# design.net
KiCad netlist of a schematic drawn in Altium Designer
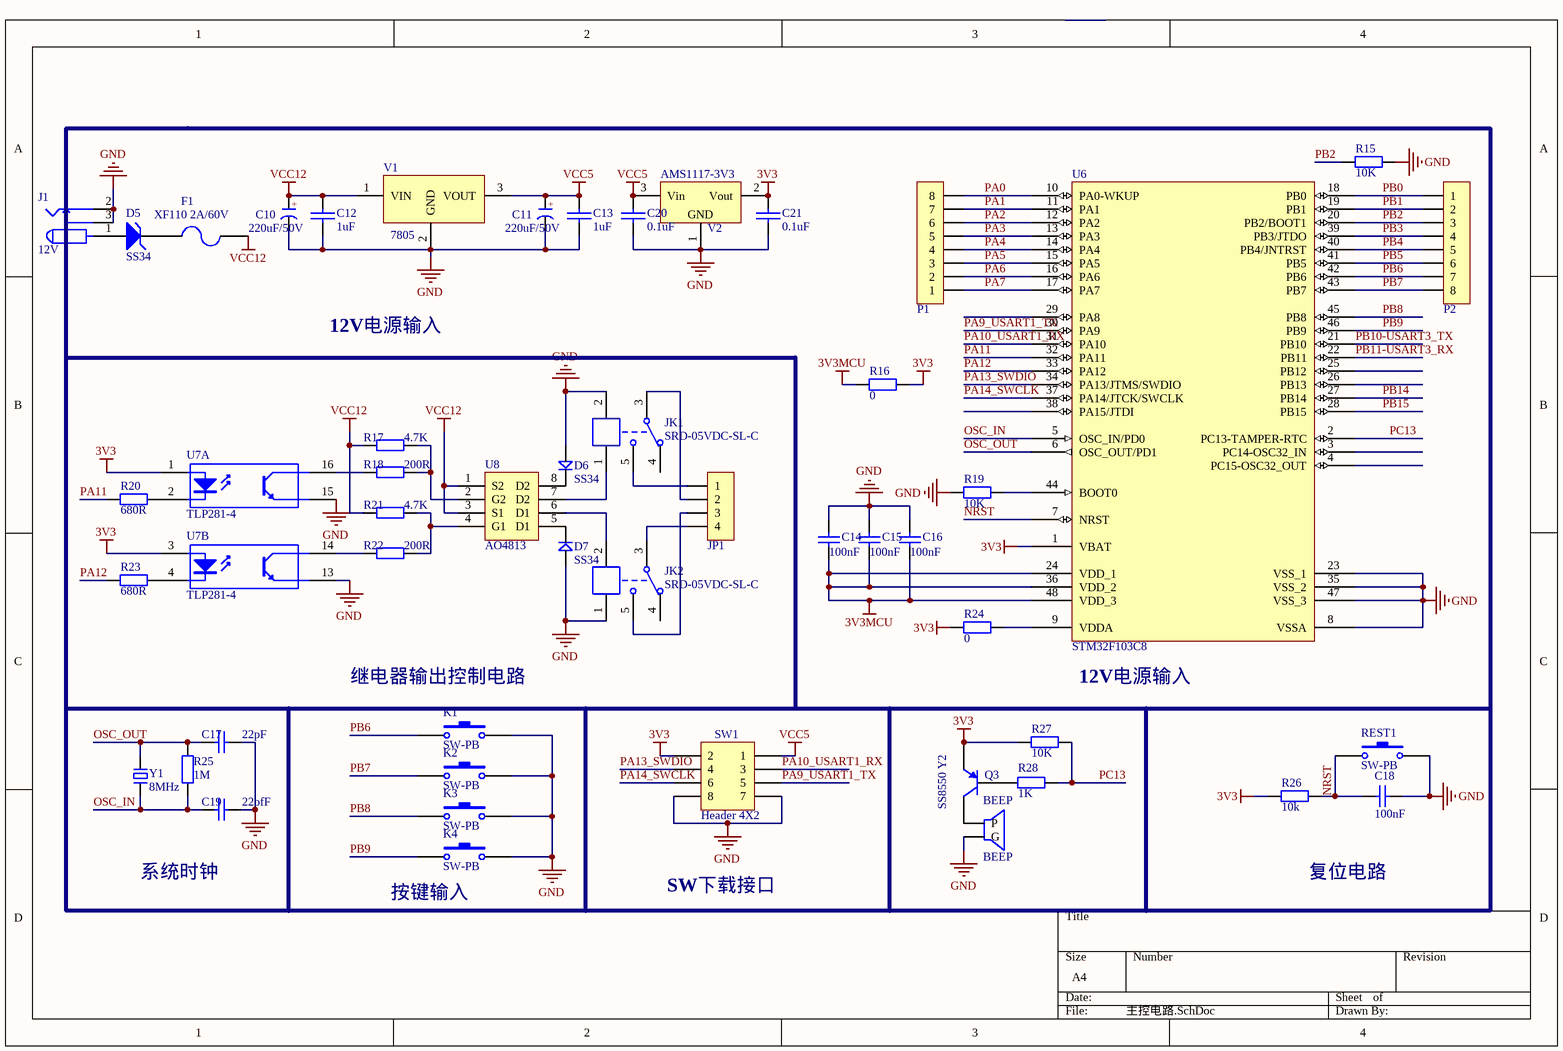
[diagram p0: 主控电路.SchDoc]

(export (version "E")
  (design (tool "Eeschema 10.0.6"))
  (components
    (comp (ref "BEEP")
      (value "BEEP")
      (footprint "BUZZER")
      (libsource (lib "Explorer STM32F407封装库") (part "BEEP"))
    )
    (comp (ref "C10")
      (value "220uF/50V")
      (footprint "CAP 3.5*8*11.5 - BK")
      (description "直插电解电容")
      (fields (field (name "版权归属") "源创客"))
      (libsource (lib "3.1   - 电阻-电容-电感") (part "C-CAP"))
    )
    (comp (ref "C11")
      (value "220uF/50V")
      (footprint "CAP 3.5*8*11.5 - BK")
      (description "直插电解电容")
      (fields (field (name "版权归属") "源创客"))
      (libsource (lib "3.1   - 电阻-电容-电感") (part "C-CAP"))
    )
    (comp (ref "C12")
      (value "1uF")
      (footprint "LC-0603_C")
      (description "Capacitor 0805")
      (libsource (lib "CD's_LIB_2018") (part "0805C"))
    )
    (comp (ref "C13")
      (value "1uF")
      (footprint "LC-0603_C")
      (description "Capacitor 0805")
      (libsource (lib "CD's_LIB_2018") (part "0805C"))
    )
    (comp (ref "C14")
      (value "100nF")
      (footprint "LC-0603_C")
      (description "无极性电容")
      (fields (field (name "PUBLISHER") "Altium Limited"))
      (libsource (lib "liu_2016") (part "Cap"))
    )
    (comp (ref "C15")
      (value "100nF")
      (footprint "LC-0603_C")
      (description "无极性电容")
      (fields (field (name "PUBLISHER") "Altium Limited"))
      (libsource (lib "liu_2016") (part "Cap"))
    )
    (comp (ref "C16")
      (value "100nF")
      (footprint "LC-0603_C")
      (description "无极性电容")
      (fields (field (name "PUBLISHER") "Altium Limited"))
      (libsource (lib "liu_2016") (part "Cap"))
    )
    (comp (ref "C17")
      (value "22pF")
      (footprint "LC-0603_C")
      (description "无极性电容")
      (fields (field (name "PUBLISHER") "Altium Limited"))
      (libsource (lib "liu_2016") (part "Cap"))
    )
    (comp (ref "C18")
      (value "100nF")
      (footprint "LC-0603_C")
      (description "无极性电容")
      (fields (field (name "PUBLISHER") "Altium Limited"))
      (libsource (lib "liu_2016") (part "Cap"))
    )
    (comp (ref "C19")
      (value "22pfF")
      (footprint "LC-0603_C")
      (description "无极性电容")
      (fields (field (name "PUBLISHER") "Altium Limited"))
      (libsource (lib "liu_2016") (part "Cap"))
    )
    (comp (ref "C20")
      (value "0.1uF")
      (footprint "LC-0603_C")
      (description "Capacitor 0805")
      (libsource (lib "CD's_LIB_2018") (part "0805C"))
    )
    (comp (ref "C21")
      (value "0.1uF")
      (footprint "LC-0603_C")
      (description "Capacitor 0805")
      (libsource (lib "CD's_LIB_2018") (part "0805C"))
    )
    (comp (ref "D5")
      (value "SS34")
      (footprint "D1812")
      (description "Zener Diode")
      (libsource (lib "CD's_LIB_2018") (part "1N5822"))
    )
    (comp (ref "D6") (value "SS34") (footprint "D1812") (libsource (lib "Explorer STM32F407封装库") (part "D")))
    (comp (ref "D7") (value "SS34") (footprint "D1812") (libsource (lib "Explorer STM32F407封装库") (part "D")))
    (comp (ref "F1")
      (value "XF110 2A/60V")
      (footprint "FUSE1")
      (description "Fuse")
      (libsource (lib "*") (part "FUSE2"))
    )
    (comp (ref "J1") (value "12V") (footprint "DC10B") (libsource (lib "Explorer STM32F407封装库") (part "POW")))
    (comp (ref "JK1")
      (value "SRD-05VDC-SL-C")
      (footprint "SRD-C_B")
      (description "5V一组转换")
      (fields (field (name "版权归属") "源创客"))
      (libsource (lib "7.1   - 继电器") (part "SRD-05VDC-SL-C"))
    )
    (comp (ref "JK2")
      (value "SRD-05VDC-SL-C")
      (footprint "SRD-C_B")
      (description "5V一组转换")
      (fields (field (name "版权归属") "源创客"))
      (libsource (lib "7.1   - 继电器") (part "SRD-05VDC-SL-C"))
    )
    (comp (ref "JP1")
      (value "HDR-1X4")
      (footprint "KF128-5.08-4P")
      (description "4P接插件")
      (fields (field (name "版权归属") "源创客"))
      (libsource (lib "4.10 - 接插件-脚距5.08") (part "Header 4"))
    )
    (comp (ref "K1")
      (value "SW-PB")
      (footprint "TSW DIP-6*6*5")
      (description "Switch")
      (fields (field (name "PUBLISHER") "Altium Limited"))
      (libsource (lib "PCB_Project") (part "SW-PB"))
    )
    (comp (ref "K2")
      (value "SW-PB")
      (footprint "TSW DIP-6*6*5")
      (description "Switch")
      (fields (field (name "PUBLISHER") "Altium Limited"))
      (libsource (lib "PCB_Project") (part "SW-PB"))
    )
    (comp (ref "K3")
      (value "SW-PB")
      (footprint "TSW DIP-6*6*5")
      (description "Switch")
      (fields (field (name "PUBLISHER") "Altium Limited"))
      (libsource (lib "PCB_Project") (part "SW-PB"))
    )
    (comp (ref "K4")
      (value "SW-PB")
      (footprint "TSW DIP-6*6*5")
      (description "Switch")
      (fields (field (name "PUBLISHER") "Altium Limited"))
      (libsource (lib "PCB_Project") (part "SW-PB"))
    )
    (comp (ref "P1")
      (value "HDR-1X8")
      (footprint "HDR2.54-LI-8P")
      (description "8P接插件")
      (fields (field (name "版权归属") "源创客"))
      (libsource (lib "4.5   - 接插件-脚距2.54") (part "Header 8"))
    )
    (comp (ref "P2")
      (value "HDR-1X8")
      (footprint "HDR2.54-LI-8P")
      (description "8P接插件")
      (fields (field (name "版权归属") "源创客"))
      (libsource (lib "") (part "Header 8_1"))
    )
    (comp (ref "Q3")
      (value "SS8550 Y2")
      (footprint "LC-SOT-23(SOT-23-3)")
      (description "三极管")
      (libsource (lib "Miscellaneous Devices LC") (part "SOT-23 SS8550 Y2"))
    )
    (comp (ref "R15")
      (value "10K")
      (footprint "LC-0603_R")
      (description "贴片电阻")
      (fields (field (name "PUBLISHER") "Altium Limited"))
      (libsource (lib "") (part "Res1_2"))
    )
    (comp (ref "R16")
      (value "0")
      (footprint "LC-0603_R")
      (description "贴片电阻")
      (fields (field (name "PUBLISHER") "Altium Limited"))
      (libsource (lib "liu_2016") (part "Res1"))
    )
    (comp (ref "R17")
      (value "4.7K")
      (footprint "LC-0603_R")
      (description "贴片电阻")
      (libsource (lib "Miscellaneous Devices LC") (part "0603 2.7KΩ (2701) 1%"))
    )
    (comp (ref "R18")
      (value "200R")
      (footprint "LC-0603_R")
      (description "贴片电阻")
      (libsource (lib "CD's_LIB_2018") (part "0603 2.7KΩ (2701) 1%"))
    )
    (comp (ref "R19")
      (value "10K")
      (footprint "LC-0603_R")
      (description "贴片电阻")
      (fields (field (name "PUBLISHER") "Altium Limited"))
      (libsource (lib "liu_2016") (part "Res1"))
    )
    (comp (ref "R20")
      (value "680R")
      (footprint "LC-0603_R")
      (description "贴片电阻")
      (libsource (lib "CD's_LIB_2018") (part "0603 2.7KΩ (2701) 1%"))
    )
    (comp (ref "R21")
      (value "4.7K")
      (footprint "LC-0603_R")
      (description "贴片电阻")
      (libsource (lib "Miscellaneous Devices LC") (part "0603 2.7KΩ (2701) 1%"))
    )
    (comp (ref "R22")
      (value "200R")
      (footprint "LC-0603_R")
      (description "贴片电阻")
      (libsource (lib "CD's_LIB_2018") (part "0603 2.7KΩ (2701) 1%"))
    )
    (comp (ref "R23")
      (value "680R")
      (footprint "LC-0603_R")
      (description "贴片电阻")
      (libsource (lib "CD's_LIB_2018") (part "0603 2.7KΩ (2701) 1%"))
    )
    (comp (ref "R24")
      (value "0")
      (footprint "LC-0603_R")
      (description "贴片电阻")
      (fields (field (name "PUBLISHER") "Altium Limited"))
      (libsource (lib "liu_2016") (part "Res1"))
    )
    (comp (ref "R25")
      (value "1M")
      (footprint "LC-0603_R")
      (description "贴片电阻")
      (fields (field (name "PUBLISHER") "Altium Limited"))
      (libsource (lib "") (part "Res1_1"))
    )
    (comp (ref "R26")
      (value "10k")
      (footprint "LC-0603_R")
      (description "贴片电阻")
      (fields (field (name "PUBLISHER") "Altium Limited"))
      (libsource (lib "") (part "Res1_2"))
    )
    (comp (ref "R27")
      (value "10K")
      (footprint "LC-0603_R")
      (description "贴片电阻")
      (libsource (lib "Miscellaneous Devices LC") (part "0603 1.1KΩ (1101) 1%"))
    )
    (comp (ref "R28")
      (value "1K")
      (footprint "LC-0603_R")
      (description "贴片电阻")
      (libsource (lib "Miscellaneous Devices LC") (part "0603 1.1KΩ (1101) 1%"))
    )
    (comp (ref "REST1")
      (value "SW-PB")
      (footprint "TSW DIP-6*6*5")
      (description "Switch")
      (fields (field (name "PUBLISHER") "Altium Limited"))
      (libsource (lib "PCB_Project") (part "SW-PB"))
    )
    (comp (ref "SW1")
      (value "Header 4X2")
      (footprint "HDR2.54-LI-2x4P")
      (description "Header, 4-Pin, Dual row")
      (fields (field (name "PUBLISHER") "Altium Limited"))
      (libsource (lib "Sparks") (part "Header 4X2"))
    )
    (comp (ref "U6")
      (value "STM32F103C8")
      (footprint "LQFP48 7X7_M")
      (description "Flaah:64/RAM:20/IO:36")
      (fields (field (name "版权归属") "源创客"))
      (libsource (lib "2.1   - STM32系列单片机") (part "STM32F103C8"))
    )
    (comp (ref "U7")
      (value "TLP281-4")
      (footprint "SOp-16")
      (libsource (lib "CD's_LIB_2018") (part "TP521-4_1"))
    )
    (comp (ref "U8") (value "AO4813") (footprint "SOP-8") (libsource (lib "NDS8434") (part "NDS8434")))
    (comp (ref "V1")
      (value "7805")
      (footprint "TO220A")
      (description "线性稳压芯片")
      (fields (field (name "版权归属") "源创客"))
      (libsource (lib "1.3   - 电源类芯片") (part "78xx"))
    )
    (comp (ref "V2")
      (value "AMS1117-3V3")
      (footprint "SOT223_M")
      (description "三端稳压芯片")
      (fields (field (name "版权归属") "源创客"))
      (libsource (lib "1.3   - 电源类芯片") (part "AMS1117"))
    )
    (comp (ref "Y1")
      (value "8MHz")
      (footprint "OSC HC-49S")
      (description "2脚无源脚晶振")
      (fields (field (name "版权归属") "源创客"))
      (libsource (lib "10.1 - 保险丝-晶振") (part "XTAL-2P"))
    )
  )
  (nets
    (net (code "1") (name "/NRST") (class "Default")
      (node (ref "C18") (pin "1") (pinfunction "1_1") (pintype "passive"))
      (node (ref "R26") (pin "2") (pinfunction "2_2") (pintype "passive"))
      (node (ref "REST1") (pin "1") (pinfunction "1_1") (pintype "passive"))
      (node (ref "U6") (pin "7") (pinfunction "NRST_7") (pintype "bidirectional"))
    )
    (net (code "2") (name "/OSC_IN") (class "Default")
      (node (ref "C19") (pin "1") (pinfunction "1_1") (pintype "passive"))
      (node (ref "R25") (pin "1") (pinfunction "1_1") (pintype "passive"))
      (node (ref "U6") (pin "5") (pinfunction "OSC_IN/PD0_5") (pintype "input"))
      (node (ref "Y1") (pin "1") (pinfunction "1_1") (pintype "passive"))
    )
    (net (code "3") (name "/OSC_OUT") (class "Default")
      (node (ref "C17") (pin "1") (pinfunction "1_1") (pintype "passive"))
      (node (ref "R25") (pin "2") (pinfunction "2_2") (pintype "passive"))
      (node (ref "U6") (pin "6") (pinfunction "OSC_OUT/PD1_6") (pintype "output"))
      (node (ref "Y1") (pin "2") (pinfunction "2_2") (pintype "passive"))
    )
    (net (code "4") (name "/PA0") (class "Default")
      (node (ref "P1") (pin "8") (pinfunction "8_8") (pintype "passive"))
      (node (ref "U6") (pin "10") (pinfunction "PA0-WKUP_10") (pintype "bidirectional"))
    )
    (net (code "5") (name "/PA1") (class "Default")
      (node (ref "P1") (pin "7") (pinfunction "7_7") (pintype "passive"))
      (node (ref "U6") (pin "11") (pinfunction "PA1_11") (pintype "bidirectional"))
    )
    (net (code "6") (name "/PA2") (class "Default")
      (node (ref "P1") (pin "6") (pinfunction "6_6") (pintype "passive"))
      (node (ref "U6") (pin "12") (pinfunction "PA2_12") (pintype "bidirectional"))
    )
    (net (code "7") (name "/PA3") (class "Default")
      (node (ref "P1") (pin "5") (pinfunction "5_5") (pintype "passive"))
      (node (ref "U6") (pin "13") (pinfunction "PA3_13") (pintype "bidirectional"))
    )
    (net (code "8") (name "/PA4") (class "Default")
      (node (ref "P1") (pin "4") (pinfunction "4_4") (pintype "passive"))
      (node (ref "U6") (pin "14") (pinfunction "PA4_14") (pintype "bidirectional"))
    )
    (net (code "9") (name "/PA5") (class "Default")
      (node (ref "P1") (pin "3") (pinfunction "3_3") (pintype "passive"))
      (node (ref "U6") (pin "15") (pinfunction "PA5_15") (pintype "bidirectional"))
    )
    (net (code "10") (name "/PA6") (class "Default")
      (node (ref "P1") (pin "2") (pinfunction "2_2") (pintype "passive"))
      (node (ref "U6") (pin "16") (pinfunction "PA6_16") (pintype "bidirectional"))
    )
    (net (code "11") (name "/PA7") (class "Default")
      (node (ref "P1") (pin "1") (pinfunction "1_1") (pintype "passive"))
      (node (ref "U6") (pin "17") (pinfunction "PA7_17") (pintype "bidirectional"))
    )
    (net (code "12") (name "/PA9_USART1_TX") (class "Default")
      (node (ref "SW1") (pin "5") (pinfunction "5_5") (pintype "passive"))
      (node (ref "U6") (pin "30") (pinfunction "PA9_30") (pintype "bidirectional"))
    )
    (net (code "13") (name "/PA10_USART1_RX") (class "Default")
      (node (ref "SW1") (pin "3") (pinfunction "3_3") (pintype "passive"))
      (node (ref "U6") (pin "31") (pinfunction "PA10_31") (pintype "bidirectional"))
    )
    (net (code "14") (name "/PA11") (class "Default")
      (node (ref "R20") (pin "1") (pinfunction "1_1") (pintype "passive"))
      (node (ref "U6") (pin "32") (pinfunction "PA11_32") (pintype "bidirectional"))
    )
    (net (code "15") (name "/PA12") (class "Default")
      (node (ref "R23") (pin "1") (pinfunction "1_1") (pintype "passive"))
      (node (ref "U6") (pin "33") (pinfunction "PA12_33") (pintype "bidirectional"))
    )
    (net (code "16") (name "/PA13_SWDIO") (class "Default")
      (node (ref "SW1") (pin "4") (pinfunction "4_4") (pintype "passive"))
      (node (ref "U6") (pin "34") (pinfunction "PA13/JTMS/SWDIO_34") (pintype "bidirectional"))
    )
    (net (code "17") (name "/PA14_SWCLK") (class "Default")
      (node (ref "SW1") (pin "6") (pinfunction "6_6") (pintype "passive"))
      (node (ref "U6") (pin "37") (pinfunction "PA14/JTCK/SWCLK_37") (pintype "bidirectional"))
    )
    (net (code "18") (name "/PB0") (class "Default")
      (node (ref "P2") (pin "1") (pinfunction "1_1") (pintype "passive"))
      (node (ref "U6") (pin "18") (pinfunction "PB0_18") (pintype "bidirectional"))
    )
    (net (code "19") (name "/PB1") (class "Default")
      (node (ref "P2") (pin "2") (pinfunction "2_2") (pintype "passive"))
      (node (ref "U6") (pin "19") (pinfunction "PB1_19") (pintype "bidirectional"))
    )
    (net (code "20") (name "/PB2") (class "Default")
      (node (ref "P2") (pin "3") (pinfunction "3_3") (pintype "passive"))
      (node (ref "R15") (pin "1") (pinfunction "1_1") (pintype "passive"))
      (node (ref "U6") (pin "20") (pinfunction "PB2/BOOT1_20") (pintype "bidirectional"))
    )
    (net (code "21") (name "/PB3") (class "Default")
      (node (ref "P2") (pin "4") (pinfunction "4_4") (pintype "passive"))
      (node (ref "U6") (pin "39") (pinfunction "PB3/JTDO_39") (pintype "bidirectional"))
    )
    (net (code "22") (name "/PB4") (class "Default")
      (node (ref "P2") (pin "5") (pinfunction "5_5") (pintype "passive"))
      (node (ref "U6") (pin "40") (pinfunction "PB4/JNTRST_40") (pintype "bidirectional"))
    )
    (net (code "23") (name "/PB5") (class "Default")
      (node (ref "P2") (pin "6") (pinfunction "6_6") (pintype "passive"))
      (node (ref "U6") (pin "41") (pinfunction "PB5_41") (pintype "bidirectional"))
    )
    (net (code "24") (name "/PB6") (class "Default")
      (node (ref "K1") (pin "1") (pinfunction "1_1") (pintype "passive"))
      (node (ref "P2") (pin "7") (pinfunction "7_7") (pintype "passive"))
      (node (ref "U6") (pin "42") (pinfunction "PB6_42") (pintype "bidirectional"))
    )
    (net (code "25") (name "/PB7") (class "Default")
      (node (ref "K2") (pin "1") (pinfunction "1_1") (pintype "passive"))
      (node (ref "P2") (pin "8") (pinfunction "8_8") (pintype "passive"))
      (node (ref "U6") (pin "43") (pinfunction "PB7_43") (pintype "bidirectional"))
    )
    (net (code "26") (name "/PB8") (class "Default")
      (node (ref "K3") (pin "1") (pinfunction "1_1") (pintype "passive"))
      (node (ref "U6") (pin "45") (pinfunction "PB8_45") (pintype "bidirectional"))
    )
    (net (code "27") (name "/PB9") (class "Default")
      (node (ref "K4") (pin "1") (pinfunction "1_1") (pintype "passive"))
      (node (ref "U6") (pin "46") (pinfunction "PB9_46") (pintype "bidirectional"))
    )
    (net (code "28") (name "/PB10-USART3_TX") (class "Default")
      (node (ref "U6") (pin "21") (pinfunction "PB10_21") (pintype "bidirectional"))
    )
    (net (code "29") (name "/PB11-USART3_RX") (class "Default")
      (node (ref "U6") (pin "22") (pinfunction "PB11_22") (pintype "bidirectional"))
    )
    (net (code "30") (name "/PB14") (class "Default")
      (node (ref "U6") (pin "27") (pinfunction "PB14_27") (pintype "bidirectional"))
    )
    (net (code "31") (name "/PB15") (class "Default")
      (node (ref "U6") (pin "28") (pinfunction "PB15_28") (pintype "bidirectional"))
    )
    (net (code "32") (name "/PC13") (class "Default")
      (node (ref "R27") (pin "1") (pinfunction "1_1") (pintype "passive"))
      (node (ref "R28") (pin "1") (pinfunction "1_1") (pintype "passive"))
      (node (ref "U6") (pin "2") (pinfunction "PC13-TAMPER-RTC_2") (pintype "bidirectional"))
    )
    (net (code "33") (name "3V3") (class "Default")
      (node (ref "C21") (pin "2") (pinfunction "2_2") (pintype "passive"))
      (node (ref "Q3") (pin "2") (pinfunction "E_2") (pintype "passive"))
      (node (ref "R16") (pin "1") (pinfunction "1_1") (pintype "passive"))
      (node (ref "R24") (pin "2") (pinfunction "2_2") (pintype "passive"))
      (node (ref "R26") (pin "1") (pinfunction "1_1") (pintype "passive"))
      (node (ref "R27") (pin "2") (pinfunction "2_2") (pintype "passive"))
      (node (ref "SW1") (pin "2") (pinfunction "2_2") (pintype "passive"))
      (node (ref "U6") (pin "1") (pinfunction "VBAT_1") (pintype "power_in"))
      (node (ref "U7") (pin "1") (pinfunction "A_1") (pintype "passive"))
      (node (ref "U7") (pin "3") (pinfunction "A_3") (pintype "passive"))
      (node (ref "V2") (pin "2") (pinfunction "Vout_2") (pintype "passive"))
    )
    (net (code "34") (name "3V3MCU") (class "Default")
      (node (ref "C14") (pin "1") (pinfunction "1_1") (pintype "passive"))
      (node (ref "C15") (pin "1") (pinfunction "1_1") (pintype "passive"))
      (node (ref "C16") (pin "1") (pinfunction "1_1") (pintype "passive"))
      (node (ref "R16") (pin "2") (pinfunction "2_2") (pintype "passive"))
      (node (ref "U6") (pin "24") (pinfunction "VDD_1_24") (pintype "power_in"))
      (node (ref "U6") (pin "36") (pinfunction "VDD_2_36") (pintype "power_in"))
      (node (ref "U6") (pin "48") (pinfunction "VDD_3_48") (pintype "power_in"))
    )
    (net (code "35") (name "GND") (class "Default")
      (node (ref "BEEP") (pin "2") (pinfunction "G_2") (pintype "passive"))
      (node (ref "C10") (pin "2") (pinfunction "K_2") (pintype "passive"))
      (node (ref "C11") (pin "2") (pinfunction "K_2") (pintype "passive"))
      (node (ref "C12") (pin "1") (pinfunction "1_1") (pintype "passive"))
      (node (ref "C13") (pin "1") (pinfunction "1_1") (pintype "passive"))
      (node (ref "C14") (pin "2") (pinfunction "2_2") (pintype "passive"))
      (node (ref "C15") (pin "2") (pinfunction "2_2") (pintype "passive"))
      (node (ref "C16") (pin "2") (pinfunction "2_2") (pintype "passive"))
      (node (ref "C17") (pin "2") (pinfunction "2_2") (pintype "passive"))
      (node (ref "C18") (pin "2") (pinfunction "2_2") (pintype "passive"))
      (node (ref "C19") (pin "2") (pinfunction "2_2") (pintype "passive"))
      (node (ref "C20") (pin "1") (pinfunction "1_1") (pintype "passive"))
      (node (ref "C21") (pin "1") (pinfunction "1_1") (pintype "passive"))
      (node (ref "D6") (pin "1") (pintype "passive"))
      (node (ref "D7") (pin "1") (pintype "passive"))
      (node (ref "J1") (pin "2") (pintype "passive"))
      (node (ref "J1") (pin "3") (pintype "passive"))
      (node (ref "JK1") (pin "2") (pinfunction "2_2") (pintype "passive"))
      (node (ref "JK2") (pin "1") (pinfunction "1_1") (pintype "passive"))
      (node (ref "K1") (pin "2") (pinfunction "2_2") (pintype "passive"))
      (node (ref "K2") (pin "2") (pinfunction "2_2") (pintype "passive"))
      (node (ref "K3") (pin "2") (pinfunction "2_2") (pintype "passive"))
      (node (ref "K4") (pin "2") (pinfunction "2_2") (pintype "passive"))
      (node (ref "R15") (pin "2") (pinfunction "2_2") (pintype "passive"))
      (node (ref "R19") (pin "2") (pinfunction "2_2") (pintype "passive"))
      (node (ref "REST1") (pin "2") (pinfunction "2_2") (pintype "passive"))
      (node (ref "SW1") (pin "7") (pinfunction "7_7") (pintype "passive"))
      (node (ref "SW1") (pin "8") (pinfunction "8_8") (pintype "passive"))
      (node (ref "U6") (pin "23") (pinfunction "VSS_1_23") (pintype "power_in"))
      (node (ref "U6") (pin "35") (pinfunction "VSS_2_35") (pintype "power_in"))
      (node (ref "U6") (pin "47") (pinfunction "VSS_3_47") (pintype "power_in"))
      (node (ref "U6") (pin "8") (pinfunction "VSSA_8") (pintype "power_in"))
      (node (ref "U7") (pin "13") (pinfunction "E_13") (pintype "passive"))
      (node (ref "U7") (pin "15") (pinfunction "E_15") (pintype "passive"))
      (node (ref "V1") (pin "2") (pinfunction "GND_2") (pintype "passive"))
      (node (ref "V2") (pin "1") (pinfunction "GND_1") (pintype "passive"))
    )
    (net (code "36") (name "Net-(BEEP-P)") (class "Default")
      (node (ref "BEEP") (pin "1") (pinfunction "P_1") (pintype "passive"))
      (node (ref "Q3") (pin "3") (pinfunction "C_3") (pintype "passive"))
    )
    (net (code "37") (name "Net-(D5-A)") (class "Default")
      (node (ref "D5") (pin "1") (pinfunction "A_1") (pintype "passive"))
      (node (ref "J1") (pin "1") (pintype "passive"))
    )
    (net (code "38") (name "Net-(D5-K)") (class "Default")
      (node (ref "D5") (pin "2") (pinfunction "K_2") (pintype "passive"))
      (node (ref "F1") (pin "1") (pinfunction "1_1") (pintype "passive"))
    )
    (net (code "39") (name "Net-(D6-Pad2)") (class "Default")
      (node (ref "D6") (pin "2") (pintype "passive"))
      (node (ref "U8") (pin "8") (pinfunction "D2_8") (pintype "passive"))
    )
    (net (code "40") (name "Net-(D7-Pad2)") (class "Default")
      (node (ref "D7") (pin "2") (pintype "passive"))
      (node (ref "U8") (pin "5") (pinfunction "D1_5") (pintype "passive"))
    )
    (net (code "41") (name "Net-(JK1-Pad1)") (class "Default")
      (node (ref "JK1") (pin "1") (pinfunction "1_1") (pintype "passive"))
      (node (ref "U8") (pin "7") (pinfunction "D2_7") (pintype "passive"))
    )
    (net (code "42") (name "Net-(JK1-Pad3)") (class "Default")
      (node (ref "JK1") (pin "3") (pinfunction "3_3") (pintype "passive"))
      (node (ref "JP1") (pin "2") (pinfunction "2_2") (pintype "passive"))
    )
    (net (code "43") (name "Net-(JK1-Pad5)") (class "Default")
      (node (ref "JK1") (pin "5") (pinfunction "5_5") (pintype "passive"))
      (node (ref "JP1") (pin "1") (pinfunction "1_1") (pintype "passive"))
    )
    (net (code "44") (name "Net-(JK2-Pad2)") (class "Default")
      (node (ref "JK2") (pin "2") (pinfunction "2_2") (pintype "passive"))
      (node (ref "U8") (pin "6") (pinfunction "D1_6") (pintype "passive"))
    )
    (net (code "45") (name "Net-(JK2-Pad3)") (class "Default")
      (node (ref "JK2") (pin "3") (pinfunction "3_3") (pintype "passive"))
      (node (ref "JP1") (pin "4") (pinfunction "4_4") (pintype "passive"))
    )
    (net (code "46") (name "Net-(JK2-Pad5)") (class "Default")
      (node (ref "JK2") (pin "5") (pinfunction "5_5") (pintype "passive"))
      (node (ref "JP1") (pin "3") (pinfunction "3_3") (pintype "passive"))
    )
    (net (code "47") (name "Net-(Q3-B)") (class "Default")
      (node (ref "Q3") (pin "1") (pinfunction "B_1") (pintype "passive"))
      (node (ref "R28") (pin "2") (pinfunction "2_2") (pintype "passive"))
    )
    (net (code "48") (name "Net-(U6-BOOT0)") (class "Default")
      (node (ref "R19") (pin "1") (pinfunction "1_1") (pintype "passive"))
      (node (ref "U6") (pin "44") (pinfunction "BOOT0_44") (pintype "input"))
    )
    (net (code "49") (name "Net-(U6-VDDA)") (class "Default")
      (node (ref "R24") (pin "1") (pinfunction "1_1") (pintype "passive"))
      (node (ref "U6") (pin "9") (pinfunction "VDDA_9") (pintype "power_in"))
    )
    (net (code "50") (name "Net-(U7A-C)") (class "Default")
      (node (ref "R18") (pin "1") (pinfunction "1_1") (pintype "passive"))
      (node (ref "U7") (pin "16") (pinfunction "C_16") (pintype "passive"))
    )
    (net (code "51") (name "Net-(U7A-K)") (class "Default")
      (node (ref "R20") (pin "2") (pinfunction "2_2") (pintype "passive"))
      (node (ref "U7") (pin "2") (pinfunction "K_2") (pintype "passive"))
    )
    (net (code "52") (name "Net-(U7B-C)") (class "Default")
      (node (ref "R22") (pin "1") (pinfunction "1_1") (pintype "passive"))
      (node (ref "U7") (pin "14") (pinfunction "C_14") (pintype "passive"))
    )
    (net (code "53") (name "Net-(U7B-K)") (class "Default")
      (node (ref "R23") (pin "2") (pinfunction "2_2") (pintype "passive"))
      (node (ref "U7") (pin "4") (pinfunction "K_4") (pintype "passive"))
    )
    (net (code "54") (name "Net-(U8-G1)") (class "Default")
      (node (ref "R21") (pin "1") (pinfunction "1_1") (pintype "passive"))
      (node (ref "R22") (pin "2") (pinfunction "2_2") (pintype "passive"))
      (node (ref "U8") (pin "4") (pinfunction "G1_4") (pintype "passive"))
    )
    (net (code "55") (name "Net-(U8-G2)") (class "Default")
      (node (ref "R17") (pin "1") (pinfunction "1_1") (pintype "passive"))
      (node (ref "R18") (pin "2") (pinfunction "2_2") (pintype "passive"))
      (node (ref "U8") (pin "2") (pinfunction "G2_2") (pintype "passive"))
    )
    (net (code "56") (name "VCC5") (class "Default")
      (node (ref "C11") (pin "1") (pinfunction "A_1") (pintype "passive"))
      (node (ref "C13") (pin "2") (pinfunction "2_2") (pintype "passive"))
      (node (ref "C20") (pin "2") (pinfunction "2_2") (pintype "passive"))
      (node (ref "SW1") (pin "1") (pinfunction "1_1") (pintype "passive"))
      (node (ref "V1") (pin "3") (pinfunction "VOUT_3") (pintype "passive"))
      (node (ref "V2") (pin "3") (pinfunction "Vin_3") (pintype "passive"))
    )
    (net (code "57") (name "VCC12") (class "Default")
      (node (ref "C10") (pin "1") (pinfunction "A_1") (pintype "passive"))
      (node (ref "C12") (pin "2") (pinfunction "2_2") (pintype "passive"))
      (node (ref "F1") (pin "2") (pinfunction "2_2") (pintype "passive"))
      (node (ref "R17") (pin "2") (pinfunction "2_2") (pintype "passive"))
      (node (ref "R21") (pin "2") (pinfunction "2_2") (pintype "passive"))
      (node (ref "U8") (pin "1") (pinfunction "S2_1") (pintype "passive"))
      (node (ref "U8") (pin "3") (pinfunction "S1_3") (pintype "passive"))
      (node (ref "V1") (pin "1") (pinfunction "VIN_1") (pintype "passive"))
    )
    (net (code "58") (name "unconnected-(JK1-Pad4)") (class "Default")
      (node (ref "JK1") (pin "4") (pinfunction "4_4") (pintype "passive"))
    )
    (net (code "59") (name "unconnected-(JK2-Pad4)") (class "Default")
      (node (ref "JK2") (pin "4") (pinfunction "4_4") (pintype "passive"))
    )
    (net (code "60") (name "unconnected-(U6-PA8-Pad29)") (class "Default")
      (node (ref "U6") (pin "29") (pinfunction "PA8_29") (pintype "bidirectional"))
    )
    (net (code "61") (name "unconnected-(U6-PA15{slash}JTDI-Pad38)") (class "Default")
      (node (ref "U6") (pin "38") (pinfunction "PA15/JTDI_38") (pintype "bidirectional"))
    )
    (net (code "62") (name "unconnected-(U6-PB12-Pad25)") (class "Default")
      (node (ref "U6") (pin "25") (pinfunction "PB12_25") (pintype "bidirectional"))
    )
    (net (code "63") (name "unconnected-(U6-PB13-Pad26)") (class "Default")
      (node (ref "U6") (pin "26") (pinfunction "PB13_26") (pintype "bidirectional"))
    )
    (net (code "64") (name "unconnected-(U6-PC14-OSC32_IN-Pad3)") (class "Default")
      (node (ref "U6") (pin "3") (pinfunction "PC14-OSC32_IN_3") (pintype "bidirectional"))
    )
    (net (code "65") (name "unconnected-(U6-PC15-OSC32_OUT-Pad4)") (class "Default")
      (node (ref "U6") (pin "4") (pinfunction "PC15-OSC32_OUT_4") (pintype "bidirectional"))
    )
  )
)
